# PortiloopV2Altium_Sch.net
KiCad netlist of a schematic drawn in Altium Designer
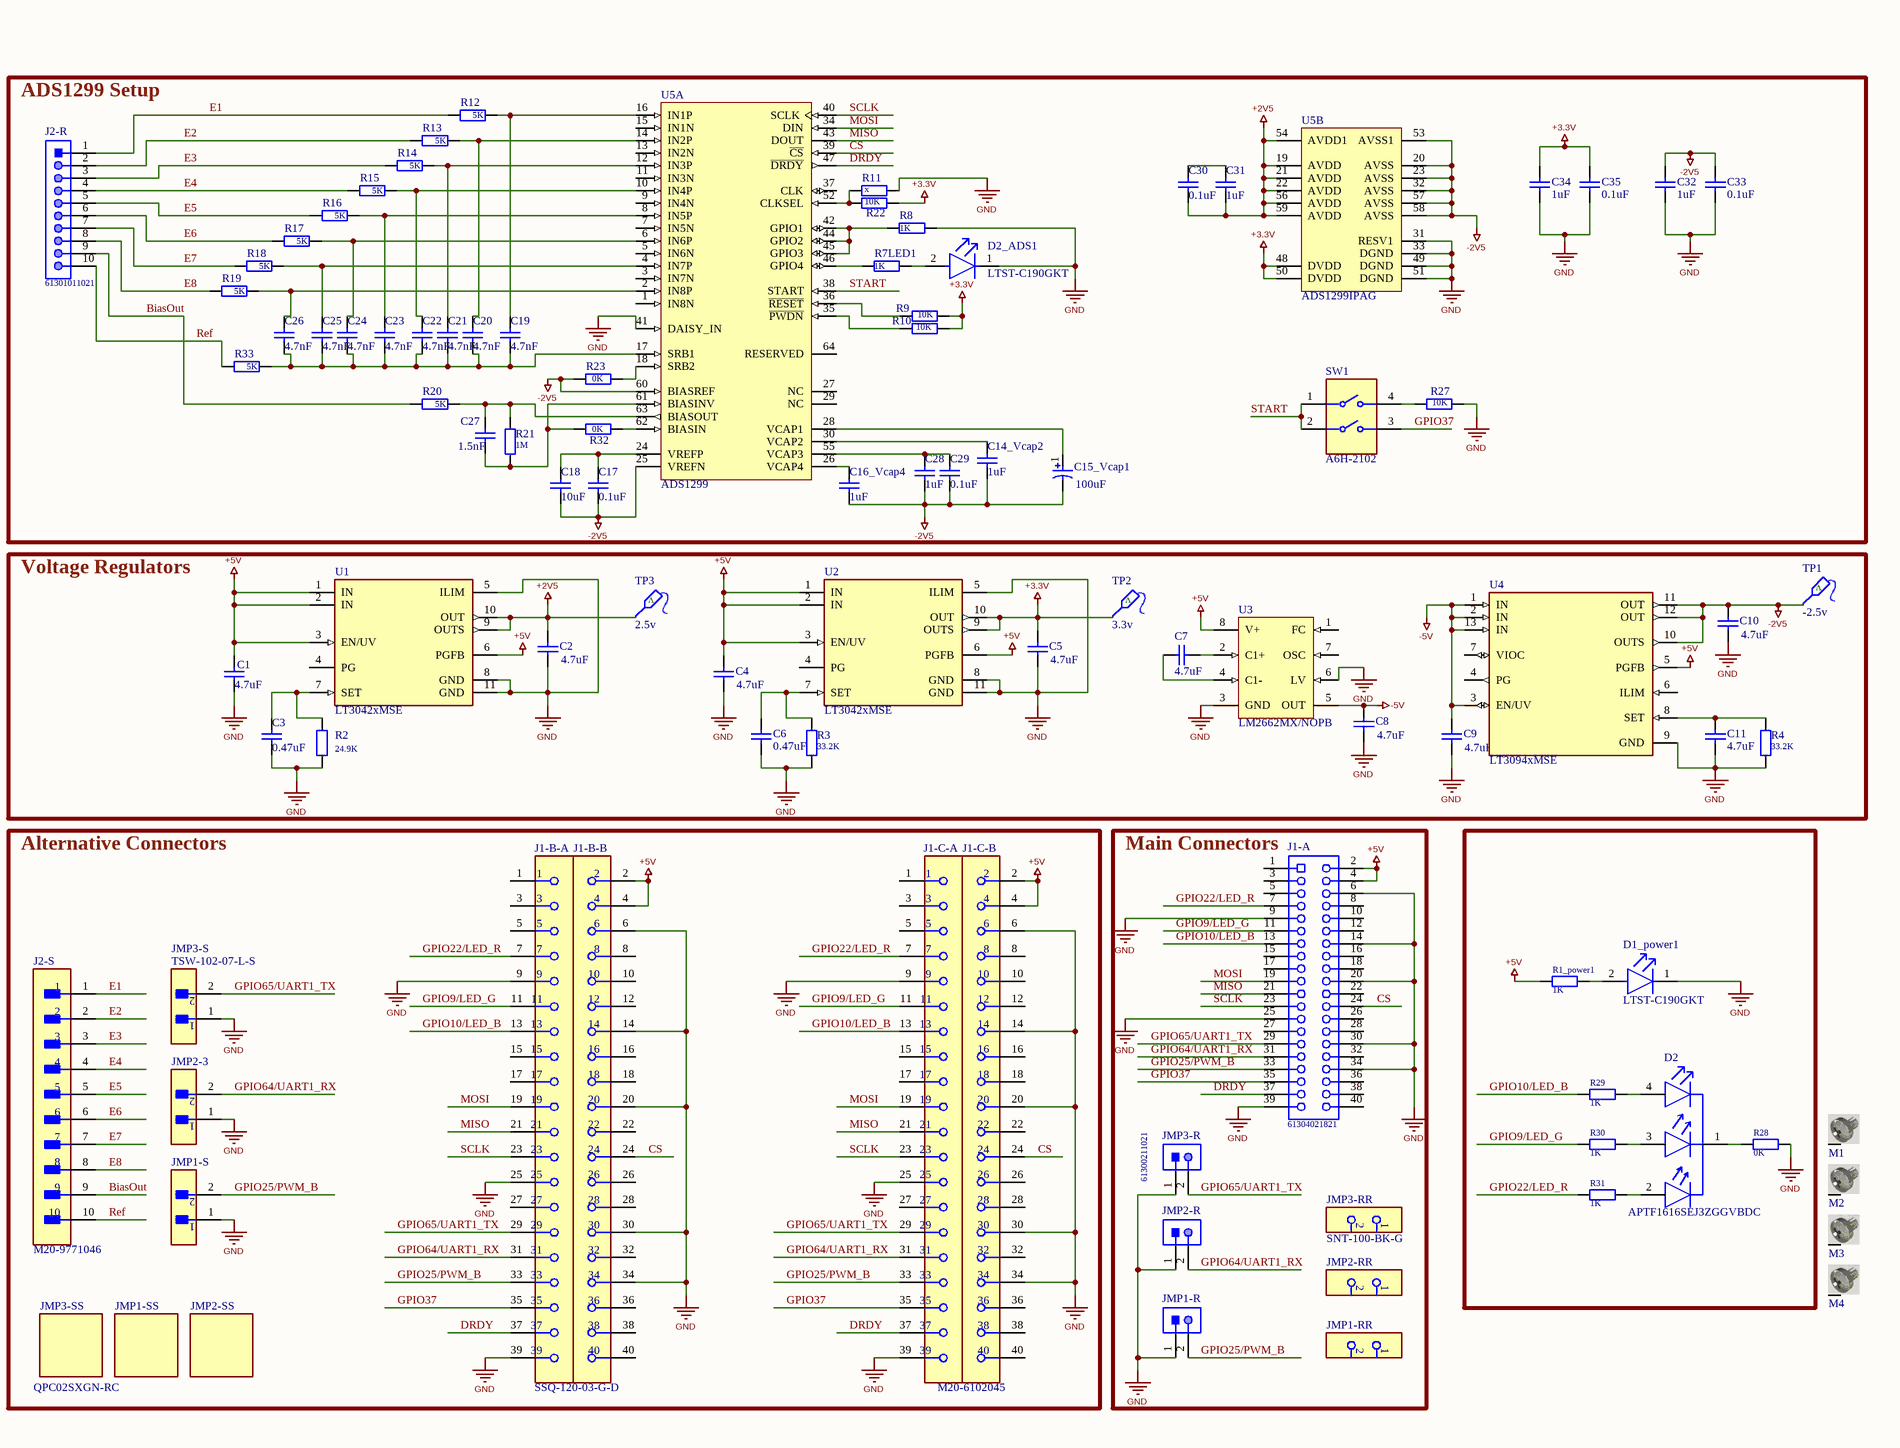
[diagram p0: PortiloopV2Altium_Sch.SchDoc, right]

(export (version "E")
  (design (tool "Eeschema 10.0.6"))
  (components
    (comp (ref "C1")
      (value "4.7uF")
      (footprint "C1206")
      (fields (field (name "Comment") "4.7mkf") (field (name "PUBLISHER") "Altium Limited"))
      (libsource (lib "Miscellaneous Devices") (part "Cap Semi"))
    )
    (comp (ref "C2")
      (value "4.7uF")
      (footprint "C1206")
      (fields (field (name "Comment") "4.7mkf") (field (name "PUBLISHER") "Altium Limited"))
      (libsource (lib "Miscellaneous Devices") (part "Cap Semi"))
    )
    (comp (ref "C3")
      (value "0.47uF")
      (footprint "1608[0603]")
      (fields (field (name "Comment") "0.47mkf") (field (name "PUBLISHER") "Altium Limited"))
      (libsource (lib "Miscellaneous Devices") (part "Cap Semi"))
    )
    (comp (ref "C4")
      (value "4.7uF")
      (footprint "C1206")
      (fields (field (name "Comment") "4.7mkf") (field (name "PUBLISHER") "Altium Limited"))
      (libsource (lib "Miscellaneous Devices") (part "Cap Semi"))
    )
    (comp (ref "C5")
      (value "4.7uF")
      (footprint "C1206")
      (fields (field (name "Comment") "4.7mkf") (field (name "PUBLISHER") "Altium Limited"))
      (libsource (lib "Miscellaneous Devices") (part "Cap Semi"))
    )
    (comp (ref "C6")
      (value "0.47uF")
      (footprint "1608[0603]")
      (fields (field (name "Comment") "0.47mkf") (field (name "PUBLISHER") "Altium Limited"))
      (libsource (lib "Miscellaneous Devices") (part "Cap Semi"))
    )
    (comp (ref "C7")
      (value "4.7uF")
      (footprint "C1206")
      (fields (field (name "Comment") "4.7mkf") (field (name "PUBLISHER") "Altium Limited"))
      (libsource (lib "Miscellaneous Devices") (part "Cap Semi"))
    )
    (comp (ref "C8")
      (value "4.7uF")
      (footprint "C1206")
      (fields (field (name "Comment") "4.7mkf") (field (name "PUBLISHER") "Altium Limited"))
      (libsource (lib "Miscellaneous Devices") (part "Cap Semi"))
    )
    (comp (ref "C9")
      (value "4.7uF")
      (footprint "C1206")
      (fields (field (name "Comment") "4.7mkf") (field (name "PUBLISHER") "Altium Limited"))
      (libsource (lib "Miscellaneous Devices") (part "Cap Semi"))
    )
    (comp (ref "C10")
      (value "4.7uF")
      (footprint "C1206")
      (fields (field (name "Comment") "4.7mkf") (field (name "PUBLISHER") "Altium Limited"))
      (libsource (lib "Miscellaneous Devices") (part "Cap Semi"))
    )
    (comp (ref "C11")
      (value "4.7uF")
      (footprint "C1206")
      (fields (field (name "Comment") "4.7mkf") (field (name "PUBLISHER") "Altium Limited"))
      (libsource (lib "Miscellaneous Devices") (part "Cap Semi"))
    )
    (comp (ref "C14_Vcap2")
      (value "1uF")
      (footprint "1608[0603]")
      (fields (field (name "Comment") "1mkf") (field (name "PUBLISHER") "Altium Limited"))
      (libsource (lib "Miscellaneous Devices") (part "Cap Semi"))
    )
    (comp (ref "C15_Vcap1")
      (value "100mkf")
      (footprint "KEMT-T491-D_M")
      (description "Capacitor, Tantalum, 100 uF, +/- 10%, -55 to 125 degC, 2-Pin SMD, RoHS, Tape and Reel")
      (fields (field (name "TOLERANCE") "20%") (field (name "CAPACITANCE") "100uF"))
      (libsource (lib "Altium Content Vault") (part "CAP-P-2"))
    )
    (comp (ref "C16_Vcap4")
      (value "1uF")
      (footprint "1608[0603]")
      (fields (field (name "Comment") "1mkf") (field (name "PUBLISHER") "Altium Limited"))
      (libsource (lib "Miscellaneous Devices") (part "Cap Semi"))
    )
    (comp (ref "C17")
      (value "0.1uF")
      (footprint "1608[0603]")
      (fields (field (name "Comment") "0.1mkf") (field (name "PUBLISHER") "Altium Limited"))
      (libsource (lib "Miscellaneous Devices") (part "Cap Semi"))
    )
    (comp (ref "C18")
      (value "10uF")
      (footprint "C1206")
      (fields (field (name "Comment") "10mkf") (field (name "PUBLISHER") "Altium Limited"))
      (libsource (lib "Miscellaneous Devices") (part "Cap Semi"))
    )
    (comp (ref "C19")
      (value "4.7nF")
      (footprint "1608[0603]")
      (fields (field (name "Comment") "4.7nf") (field (name "PUBLISHER") "Altium Limited"))
      (libsource (lib "Miscellaneous Devices") (part "Cap Semi"))
    )
    (comp (ref "C20")
      (value "4.7nF")
      (footprint "1608[0603]")
      (fields (field (name "Comment") "4.7nf") (field (name "PUBLISHER") "Altium Limited"))
      (libsource (lib "Miscellaneous Devices") (part "Cap Semi"))
    )
    (comp (ref "C21")
      (value "4.7nF")
      (footprint "1608[0603]")
      (fields (field (name "Comment") "4.7nf") (field (name "PUBLISHER") "Altium Limited"))
      (libsource (lib "Miscellaneous Devices") (part "Cap Semi"))
    )
    (comp (ref "C22")
      (value "4.7nF")
      (footprint "1608[0603]")
      (fields (field (name "Comment") "4.7nf") (field (name "PUBLISHER") "Altium Limited"))
      (libsource (lib "Miscellaneous Devices") (part "Cap Semi"))
    )
    (comp (ref "C23")
      (value "4.7nF")
      (footprint "1608[0603]")
      (fields (field (name "Comment") "4.7nf") (field (name "PUBLISHER") "Altium Limited"))
      (libsource (lib "Miscellaneous Devices") (part "Cap Semi"))
    )
    (comp (ref "C24")
      (value "4.7nF")
      (footprint "1608[0603]")
      (fields (field (name "Comment") "4.7nf") (field (name "PUBLISHER") "Altium Limited"))
      (libsource (lib "Miscellaneous Devices") (part "Cap Semi"))
    )
    (comp (ref "C25")
      (value "4.7nF")
      (footprint "1608[0603]")
      (fields (field (name "Comment") "4.7nf") (field (name "PUBLISHER") "Altium Limited"))
      (libsource (lib "Miscellaneous Devices") (part "Cap Semi"))
    )
    (comp (ref "C26")
      (value "4.7nF")
      (footprint "1608[0603]")
      (fields (field (name "Comment") "4.7nf") (field (name "PUBLISHER") "Altium Limited"))
      (libsource (lib "Miscellaneous Devices") (part "Cap Semi"))
    )
    (comp (ref "C27")
      (value "1.5nF")
      (footprint "1608[0603]")
      (fields (field (name "Comment") "1.5nf") (field (name "PUBLISHER") "Altium Limited"))
      (libsource (lib "Miscellaneous Devices") (part "Cap Semi"))
    )
    (comp (ref "C28")
      (value "1uF")
      (footprint "1608[0603]")
      (fields (field (name "Comment") "1mkf") (field (name "PUBLISHER") "Altium Limited"))
      (libsource (lib "Miscellaneous Devices") (part "Cap Semi"))
    )
    (comp (ref "C29")
      (value "0.1uF")
      (footprint "1608[0603]")
      (fields (field (name "Comment") "0.1mkf") (field (name "PUBLISHER") "Altium Limited"))
      (libsource (lib "Miscellaneous Devices") (part "Cap Semi"))
    )
    (comp (ref "C30")
      (value "0.1uF")
      (footprint "1608[0603]")
      (fields (field (name "Comment") "0.1mkf") (field (name "PUBLISHER") "Altium Limited"))
      (libsource (lib "Miscellaneous Devices") (part "Cap Semi"))
    )
    (comp (ref "C31")
      (value "1uF")
      (footprint "1608[0603]")
      (fields (field (name "Comment") "1mkf") (field (name "PUBLISHER") "Altium Limited"))
      (libsource (lib "Miscellaneous Devices") (part "Cap Semi"))
    )
    (comp (ref "C32")
      (value "1uF")
      (footprint "1608[0603]")
      (fields (field (name "Comment") "1mkf") (field (name "PUBLISHER") "Altium Limited"))
      (libsource (lib "Miscellaneous Devices") (part "Cap Semi"))
    )
    (comp (ref "C33")
      (value "0.1uF")
      (footprint "1608[0603]")
      (fields (field (name "Comment") "0.1mkf") (field (name "PUBLISHER") "Altium Limited"))
      (libsource (lib "Miscellaneous Devices") (part "Cap Semi"))
    )
    (comp (ref "C34")
      (value "1uF")
      (footprint "1608[0603]")
      (fields (field (name "Comment") "1mkf") (field (name "PUBLISHER") "Altium Limited"))
      (libsource (lib "Miscellaneous Devices") (part "Cap Semi"))
    )
    (comp (ref "C35")
      (value "0.1uF")
      (footprint "1608[0603]")
      (fields (field (name "Comment") "0.1mkf") (field (name "PUBLISHER") "Altium Limited"))
      (libsource (lib "Miscellaneous Devices") (part "Cap Semi"))
    )
    (comp (ref "D1_power1")
      (value "LTST-C190GKT")
      (footprint "FP-LTST-C190GKT-MFG")
      (description "LED GREEN CLEAR CHIP SMD")
      (fields (field (name "VOLTAGE") "2V"))
      (libsource (lib "Altium Content Vault") (part "8706943c75ba83719d021d2fdc84c58"))
    )
    (comp (ref "D2")
      (value "APTF1616SEJ3ZGGVBDC")
      (footprint "FP-APTF1616SEJ3ZGGVBDC-MFG")
      (description "LED RGB CLEAR 4SMD")
      (libsource (lib "Altium Content Vault") (part "09016a64638d3f35f69863a61e92420"))
    )
    (comp (ref "D2_ADS1")
      (value "LTST-C190GKT")
      (footprint "FP-LTST-C190GKT-MFG")
      (description "LED GREEN CLEAR CHIP SMD")
      (fields (field (name "VOLTAGE") "2V"))
      (libsource (lib "Altium Content Vault") (part "8706943c75ba83719d021d2fdc84c58"))
    )
    (comp (ref "J1-A")
      (value "61304021821")
      (footprint "61304021821")
      (description "THT Vertical Socket Header WR-PHD, Pitch 2.54 mm, Dual Row, 40 pins")
      (fields (field (name "MANUFACTURER") "Wurth Elektronik") (field (name "PUBLISHER") "WurthElektronik"))
      (libsource (lib "Altium Content Vault") (part "WE-CN-2P-F-R40"))
    )
    (comp (ref "J1-B-")
      (value "SSQ-120-03-G-D")
      (footprint "FP-SSQ-120-03-G-D-MFG")
      (description "CONN RCPT 40POS 0.1 GOLD PCB")
      (libsource (lib "Altium Content Vault") (part "7acf1c4a8db21028d11741a46a6ec78"))
    )
    (comp (ref "J1-C-")
      (value "M20-6102045")
      (footprint "FP-M20-6102045-MFG")
      (description "CONN STKTHRU PC/104 40POS PCB")
      (libsource (lib "Altium Content Vault") (part "7acf1c4a8db21028d11741a46a6ec78"))
    )
    (comp (ref "J2-R")
      (value "61301011021")
      (footprint "61301011021")
      (description "THT Angled Pin Header WR-PHD, Pitch 2.54 mm, Single Row, 10 pins")
      (fields (field (name "MANUFACTURER") "Wurth Elektronik") (field (name "PUBLISHER") "WurthElektronik"))
      (libsource (lib "Altium Content Vault") (part "WE-CN-1P-M-R10"))
    )
    (comp (ref "J2-S")
      (value "M20-9771046")
      (footprint "FP-M20-9771046-MFG")
      (description "CONN HEADER VERT 10POS 2.54MM")
      (libsource (lib "Altium Content Vault") (part "aee40dc8b284c03a16094555aa210be"))
    )
    (comp (ref "JMP1-R")
      (value "61300211021")
      (footprint "61300211021")
      (description "THT Angled Pin Header WR-PHD, Pitch 2.54 mm, Single Row, 2 pins")
      (fields (field (name "MANUFACTURER") "Wurth Elektronik") (field (name "PUBLISHER") "WurthElektronik"))
      (libsource (lib "Altium Content Vault") (part "WE-CN-1P-M-R2"))
    )
    (comp (ref "JMP1-RR")
      (value "SNT-100-BK-G")
      (footprint "FP-SNT-100-BK-G-MFG")
      (description "CONN SHUNT 2POS")
      (libsource (lib "Altium Content Vault") (part "245d4dded57b275ea2dfe9722bb6e84"))
    )
    (comp (ref "JMP1-S")
      (value "TSW-102-07-L-S")
      (footprint "FP-TSW-102-07-L-S-MFG")
      (description "CONN HEADER VERT 2POS 2.54MM")
      (libsource (lib "Altium Content Vault") (part "3bc925449376181038e59eaffc5286c"))
    )
    (comp (ref "JMP1-SS")
      (value "QPC02SXGN-RC")
      (footprint "FP-QPC02SXGN-RC-MFG")
      (description "CONN JUMPER SHORTING .100\" GOLD")
      (fields
        (field (name "MANUFACTURER") "Sullins")
        (field (name "OCTOPART") "https://octopart.com/qpc02sxgn-rc-sullins-19878795")
      )
      (libsource (lib "Altium Content Vault") (part "87292ac8601c6cf2061292f5bede09e"))
    )
    (comp (ref "JMP2-3")
      (value "TSW-102-07-L-S")
      (footprint "FP-TSW-102-07-L-S-MFG")
      (description "CONN HEADER VERT 2POS 2.54MM")
      (libsource (lib "Altium Content Vault") (part "3bc925449376181038e59eaffc5286c"))
    )
    (comp (ref "JMP2-R")
      (value "61300211021")
      (footprint "61300211021")
      (description "THT Angled Pin Header WR-PHD, Pitch 2.54 mm, Single Row, 2 pins")
      (fields (field (name "MANUFACTURER") "Wurth Elektronik") (field (name "PUBLISHER") "WurthElektronik"))
      (libsource (lib "Altium Content Vault") (part "WE-CN-1P-M-R2"))
    )
    (comp (ref "JMP2-RR")
      (value "SNT-100-BK-G")
      (footprint "FP-SNT-100-BK-G-MFG")
      (description "CONN SHUNT 2POS")
      (libsource (lib "Altium Content Vault") (part "245d4dded57b275ea2dfe9722bb6e84"))
    )
    (comp (ref "JMP2-SS")
      (value "QPC02SXGN-RC")
      (footprint "FP-QPC02SXGN-RC-MFG")
      (description "CONN JUMPER SHORTING .100\" GOLD")
      (fields
        (field (name "MANUFACTURER") "Sullins")
        (field (name "OCTOPART") "https://octopart.com/qpc02sxgn-rc-sullins-19878795")
      )
      (libsource (lib "Altium Content Vault") (part "87292ac8601c6cf2061292f5bede09e"))
    )
    (comp (ref "JMP3-R")
      (value "61300211021")
      (footprint "61300211021")
      (description "THT Angled Pin Header WR-PHD, Pitch 2.54 mm, Single Row, 2 pins")
      (fields (field (name "MANUFACTURER") "Wurth Elektronik") (field (name "PUBLISHER") "WurthElektronik"))
      (libsource (lib "Altium Content Vault") (part "WE-CN-1P-M-R2"))
    )
    (comp (ref "JMP3-RR")
      (value "SNT-100-BK-G")
      (footprint "FP-SNT-100-BK-G-MFG")
      (description "CONN SHUNT 2POS")
      (libsource (lib "Altium Content Vault") (part "245d4dded57b275ea2dfe9722bb6e84"))
    )
    (comp (ref "JMP3-S")
      (value "TSW-102-07-L-S")
      (footprint "FP-TSW-102-07-L-S-MFG")
      (description "CONN HEADER VERT 2POS 2.54MM")
      (libsource (lib "Altium Content Vault") (part "3bc925449376181038e59eaffc5286c"))
    )
    (comp (ref "JMP3-SS")
      (value "QPC02SXGN-RC")
      (footprint "FP-QPC02SXGN-RC-MFG")
      (description "CONN JUMPER SHORTING .100\" GOLD")
      (fields
        (field (name "MANUFACTURER") "Sullins")
        (field (name "OCTOPART") "https://octopart.com/qpc02sxgn-rc-sullins-19878795")
      )
      (libsource (lib "Altium Content Vault") (part "87292ac8601c6cf2061292f5bede09e"))
    )
    (comp (ref "M1")
      (value "Screw")
      (footprint "Board Screw_No Silk")
      (description "Board Screw With Spacer")
      (libsource (lib "Lib_marjani") (part "Board Screw"))
    )
    (comp (ref "M2")
      (value "Screw")
      (footprint "Board Screw_No Silk")
      (description "Board Screw With Spacer")
      (libsource (lib "Lib_marjani") (part "Board Screw"))
    )
    (comp (ref "M3")
      (value "Screw")
      (footprint "Board Screw_No Silk")
      (description "Board Screw With Spacer")
      (libsource (lib "Lib_marjani") (part "Board Screw"))
    )
    (comp (ref "M4")
      (value "Screw")
      (footprint "Board Screw_No Silk")
      (description "Board Screw With Spacer")
      (libsource (lib "Lib_marjani") (part "Board Screw"))
    )
    (comp (ref "R1_power1")
      (value "1K")
      (footprint "1608[0603]")
      (description "Resistor")
      (fields (field (name "PUBLISHER") "Altium Limited"))
      (libsource (lib "") (part "Res2_2"))
    )
    (comp (ref "R2")
      (value "24.9K")
      (footprint "1608[0603]")
      (description "Resistor")
      (fields (field (name "PUBLISHER") "Altium Limited"))
      (libsource (lib "Miscellaneous Devices") (part "Res2"))
    )
    (comp (ref "R3")
      (value "33.2K")
      (footprint "1608[0603]")
      (description "Resistor")
      (fields (field (name "PUBLISHER") "Altium Limited"))
      (libsource (lib "Miscellaneous Devices") (part "Res2"))
    )
    (comp (ref "R4")
      (value "33.2K")
      (footprint "1608[0603]")
      (description "Resistor")
      (fields (field (name "PUBLISHER") "Altium Limited"))
      (libsource (lib "Miscellaneous Devices") (part "Res2"))
    )
    (comp (ref "R7LED1")
      (value "1K")
      (footprint "1608[0603]")
      (description "Resistor")
      (fields (field (name "PUBLISHER") "Altium Limited"))
      (libsource (lib "") (part "Res2_1"))
    )
    (comp (ref "R8")
      (value "1K")
      (footprint "1608[0603]")
      (description "Resistor")
      (fields (field (name "PUBLISHER") "Altium Limited"))
      (libsource (lib "") (part "Res2_1"))
    )
    (comp (ref "R9")
      (value "10K")
      (footprint "1608[0603]")
      (description "Resistor")
      (fields (field (name "PUBLISHER") "Altium Limited"))
      (libsource (lib "") (part "Res2_2"))
    )
    (comp (ref "R10")
      (value "10K")
      (footprint "1608[0603]")
      (description "Resistor")
      (fields (field (name "PUBLISHER") "Altium Limited"))
      (libsource (lib "") (part "Res2_2"))
    )
    (comp (ref "R11")
      (value "x")
      (footprint "1608[0603]")
      (description "Not Connected")
      (fields (field (name "PUBLISHER") "Altium Limited"))
      (libsource (lib "") (part "Res2_2"))
    )
    (comp (ref "R12")
      (value "5K")
      (footprint "1608[0603]")
      (description "Resistor")
      (fields (field (name "PUBLISHER") "Altium Limited"))
      (libsource (lib "") (part "Res2_1"))
    )
    (comp (ref "R13")
      (value "5K")
      (footprint "1608[0603]")
      (description "Resistor")
      (fields (field (name "PUBLISHER") "Altium Limited"))
      (libsource (lib "") (part "Res2_1"))
    )
    (comp (ref "R14")
      (value "5K")
      (footprint "1608[0603]")
      (description "Resistor")
      (fields (field (name "PUBLISHER") "Altium Limited"))
      (libsource (lib "") (part "Res2_1"))
    )
    (comp (ref "R15")
      (value "5K")
      (footprint "1608[0603]")
      (description "Resistor")
      (fields (field (name "PUBLISHER") "Altium Limited"))
      (libsource (lib "") (part "Res2_1"))
    )
    (comp (ref "R16")
      (value "5K")
      (footprint "1608[0603]")
      (description "Resistor")
      (fields (field (name "PUBLISHER") "Altium Limited"))
      (libsource (lib "") (part "Res2_1"))
    )
    (comp (ref "R17")
      (value "5K")
      (footprint "1608[0603]")
      (description "Resistor")
      (fields (field (name "PUBLISHER") "Altium Limited"))
      (libsource (lib "") (part "Res2_1"))
    )
    (comp (ref "R18")
      (value "5K")
      (footprint "1608[0603]")
      (description "Resistor")
      (fields (field (name "PUBLISHER") "Altium Limited"))
      (libsource (lib "") (part "Res2_1"))
    )
    (comp (ref "R19")
      (value "5K")
      (footprint "1608[0603]")
      (description "Resistor")
      (fields (field (name "PUBLISHER") "Altium Limited"))
      (libsource (lib "") (part "Res2_1"))
    )
    (comp (ref "R20")
      (value "5K")
      (footprint "1608[0603]")
      (description "Resistor")
      (fields (field (name "PUBLISHER") "Altium Limited"))
      (libsource (lib "") (part "Res2_1"))
    )
    (comp (ref "R21")
      (value "1M")
      (footprint "1608[0603]")
      (description "Resistor")
      (fields (field (name "PUBLISHER") "Altium Limited"))
      (libsource (lib "Miscellaneous Devices") (part "Res2"))
    )
    (comp (ref "R22")
      (value "10K")
      (footprint "1608[0603]")
      (description "Resistor")
      (fields (field (name "PUBLISHER") "Altium Limited"))
      (libsource (lib "") (part "Res2_2"))
    )
    (comp (ref "R23")
      (value "0K")
      (footprint "1608[0603]")
      (description "Resistor")
      (fields (field (name "PUBLISHER") "Altium Limited"))
      (libsource (lib "") (part "Res2_2"))
    )
    (comp (ref "R27")
      (value "10K")
      (footprint "1608[0603]")
      (description "Resistor")
      (fields (field (name "PUBLISHER") "Altium Limited"))
      (libsource (lib "") (part "Res2_2"))
    )
    (comp (ref "R28")
      (value "0K")
      (footprint "1608[0603]")
      (description "Resistor")
      (fields (field (name "PUBLISHER") "Altium Limited"))
      (libsource (lib "") (part "Res2_2"))
    )
    (comp (ref "R29")
      (value "1K")
      (footprint "1608[0603]")
      (description "Resistor")
      (fields (field (name "PUBLISHER") "Altium Limited"))
      (libsource (lib "") (part "Res2_2"))
    )
    (comp (ref "R30")
      (value "1K")
      (footprint "1608[0603]")
      (description "Resistor")
      (fields (field (name "PUBLISHER") "Altium Limited"))
      (libsource (lib "") (part "Res2_2"))
    )
    (comp (ref "R31")
      (value "1K")
      (footprint "1608[0603]")
      (description "Resistor")
      (fields (field (name "PUBLISHER") "Altium Limited"))
      (libsource (lib "") (part "Res2_2"))
    )
    (comp (ref "R32")
      (value "0K")
      (footprint "1608[0603]")
      (description "Resistor")
      (fields (field (name "PUBLISHER") "Altium Limited"))
      (libsource (lib "") (part "Res2_2"))
    )
    (comp (ref "R33")
      (value "5K")
      (footprint "1608[0603]")
      (description "Resistor")
      (fields (field (name "PUBLISHER") "Altium Limited"))
      (libsource (lib "") (part "Res2_1"))
    )
    (comp (ref "SW1")
      (value "A6H-2102")
      (footprint "FP-A6H-2102-MFG")
      (description "SWITCH SLIDE DIP SPST 25MA 24V")
      (libsource (lib "Altium Content Vault") (part "070a973bb9dfaf4112c7cb8da95b8f6"))
    )
    (comp (ref "TP1")
      (value "-2.5v")
      (footprint "TESTPOINT1")
      (description "Test Point")
      (libsource (lib "My Library") (part "Test Point"))
    )
    (comp (ref "TP2")
      (value "3.3v")
      (footprint "TESTPOINT1")
      (description "Test Point")
      (libsource (lib "My Library") (part "Test Point"))
    )
    (comp (ref "TP3")
      (value "2.5v")
      (footprint "TESTPOINT1")
      (description "Test Point")
      (libsource (lib "My Library") (part "Test Point"))
    )
    (comp (ref "U1")
      (value "LT3042xMSE")
      (footprint "FP-MSE-10-05-08-1664-IPC_C")
      (description "IC REG LIN POS ADJ 200MA 10MSOP")
      (libsource (lib "Altium Content Vault") (part "617b45537435f4b0c995ef5898f6a34"))
    )
    (comp (ref "U2")
      (value "LT3042xMSE")
      (footprint "FP-MSE-10-05-08-1664-IPC_C")
      (description "IC REG LIN POS ADJ 200MA 10MSOP")
      (libsource (lib "Altium Content Vault") (part "617b45537435f4b0c995ef5898f6a34"))
    )
    (comp (ref "U3")
      (value "LM2662MX/NOPB")
      (footprint "D0008A_M")
      (description "Switched Capacitor Voltage Converter, 8-pin Narrow SOIC, Pb-Free")
      (fields (field (name "MANUFACTURER") "Texas Instruments"))
      (libsource (lib "Altium Content Vault") (part "PM-CHP-LM2660M-8"))
    )
    (comp (ref "U4")
      (value "LT3094xMSE")
      (footprint "FP-MSE-12-05-08-1666-IPC_A")
      (description "IC REG LIN NEG ADJ 500MA 12MSOP")
      (libsource (lib "Altium Content Vault") (part "4f09b0e52ede19156f7e08ace673db3"))
    )
    (comp (ref "U5")
      (value "ADS1299")
      (footprint "PAG0064A_M")
      (fields (field (name "MANUFACTURER") "Texas Instruments") (field (name "PARTNUMBER") "ADS1299IPAG"))
      (libsource (lib "") (part "TI-ADS1299-PAG-64_1"))
    )
  )
  (nets
    (net (code "1") (name "+2V5") (class "Default")
      (node (ref "C2") (pin "2") (pinfunction "2_2") (pintype "passive"))
      (node (ref "C30") (pin "2") (pinfunction "2_2") (pintype "passive"))
      (node (ref "C31") (pin "2") (pinfunction "2_2") (pintype "passive"))
      (node (ref "TP3") (pin "1") (pinfunction "T_1") (pintype "passive"))
      (node (ref "U1") (pin "10") (pinfunction "OUT_10") (pintype "output"))
      (node (ref "U1") (pin "9") (pinfunction "OUTS_9") (pintype "output"))
      (node (ref "U5") (pin "19") (pinfunction "AVDD_19") (pintype "power_in"))
      (node (ref "U5") (pin "21") (pinfunction "AVDD_21") (pintype "power_in"))
      (node (ref "U5") (pin "22") (pinfunction "AVDD_22") (pintype "power_in"))
      (node (ref "U5") (pin "54") (pinfunction "AVDD1_54") (pintype "power_in"))
      (node (ref "U5") (pin "56") (pinfunction "AVDD_56") (pintype "power_in"))
      (node (ref "U5") (pin "59") (pinfunction "AVDD_59") (pintype "power_in"))
    )
    (net (code "2") (name "+3.3V") (class "Default")
      (node (ref "C34") (pin "2") (pinfunction "2_2") (pintype "passive"))
      (node (ref "C35") (pin "2") (pinfunction "2_2") (pintype "passive"))
      (node (ref "C5") (pin "2") (pinfunction "2_2") (pintype "passive"))
      (node (ref "R10") (pin "1") (pinfunction "1_1") (pintype "passive"))
      (node (ref "R22") (pin "1") (pinfunction "1_1") (pintype "passive"))
      (node (ref "R9") (pin "1") (pinfunction "1_1") (pintype "passive"))
      (node (ref "TP2") (pin "1") (pinfunction "T_1") (pintype "passive"))
      (node (ref "U2") (pin "10") (pinfunction "OUT_10") (pintype "output"))
      (node (ref "U2") (pin "9") (pinfunction "OUTS_9") (pintype "output"))
      (node (ref "U5") (pin "48") (pinfunction "DVDD_48") (pintype "power_in"))
      (node (ref "U5") (pin "50") (pinfunction "DVDD_50") (pintype "power_in"))
    )
    (net (code "3") (name "+5V") (class "Default")
      (node (ref "C1") (pin "2") (pinfunction "2_2") (pintype "passive"))
      (node (ref "C4") (pin "2") (pinfunction "2_2") (pintype "passive"))
      (node (ref "J1-A") (pin "2") (pinfunction "2_2") (pintype "passive"))
      (node (ref "J1-A") (pin "4") (pinfunction "4_4") (pintype "passive"))
      (node (ref "J1-B-") (pin "2") (pinfunction "2_2") (pintype "passive"))
      (node (ref "J1-B-") (pin "4") (pinfunction "4_4") (pintype "passive"))
      (node (ref "J1-C-") (pin "2") (pinfunction "2_2") (pintype "passive"))
      (node (ref "J1-C-") (pin "4") (pinfunction "4_4") (pintype "passive"))
      (node (ref "R1_power1") (pin "2") (pinfunction "2_2") (pintype "passive"))
      (node (ref "U1") (pin "1") (pinfunction "IN_1") (pintype "power_in"))
      (node (ref "U1") (pin "2") (pinfunction "IN_2") (pintype "power_in"))
      (node (ref "U1") (pin "3") (pinfunction "EN/UV_3") (pintype "input"))
      (node (ref "U1") (pin "6") (pinfunction "PGFB_6") (pintype "passive"))
      (node (ref "U2") (pin "1") (pinfunction "IN_1") (pintype "power_in"))
      (node (ref "U2") (pin "2") (pinfunction "IN_2") (pintype "power_in"))
      (node (ref "U2") (pin "3") (pinfunction "EN/UV_3") (pintype "input"))
      (node (ref "U2") (pin "6") (pinfunction "PGFB_6") (pintype "passive"))
      (node (ref "U3") (pin "8") (pinfunction "V+_8") (pintype "power_in"))
      (node (ref "U4") (pin "5") (pinfunction "PGFB_5") (pintype "output"))
    )
    (net (code "4") (name "-2V5") (class "Default")
      (node (ref "C10") (pin "2") (pinfunction "2_2") (pintype "passive"))
      (node (ref "C14_Vcap2") (pin "1") (pinfunction "1_1") (pintype "passive"))
      (node (ref "C15_Vcap1") (pin "2") (pinfunction "2_2") (pintype "passive"))
      (node (ref "C16_Vcap4") (pin "1") (pinfunction "1_1") (pintype "passive"))
      (node (ref "C17") (pin "2") (pinfunction "2_2") (pintype "passive"))
      (node (ref "C18") (pin "1") (pinfunction "1_1") (pintype "passive"))
      (node (ref "C28") (pin "1") (pinfunction "1_1") (pintype "passive"))
      (node (ref "C29") (pin "1") (pinfunction "1_1") (pintype "passive"))
      (node (ref "C32") (pin "2") (pinfunction "2_2") (pintype "passive"))
      (node (ref "C33") (pin "2") (pinfunction "2_2") (pintype "passive"))
      (node (ref "R23") (pin "2") (pinfunction "2_2") (pintype "passive"))
      (node (ref "TP1") (pin "1") (pinfunction "T_1") (pintype "passive"))
      (node (ref "U4") (pin "10") (pinfunction "OUTS_10") (pintype "output"))
      (node (ref "U4") (pin "11") (pinfunction "OUT_11") (pintype "output"))
      (node (ref "U4") (pin "12") (pinfunction "OUT_12") (pintype "output"))
      (node (ref "U5") (pin "20") (pinfunction "AVSS_20") (pintype "power_in"))
      (node (ref "U5") (pin "23") (pinfunction "AVSS_23") (pintype "power_in"))
      (node (ref "U5") (pin "25") (pinfunction "VREFN_25") (pintype "passive"))
      (node (ref "U5") (pin "32") (pinfunction "AVSS_32") (pintype "power_in"))
      (node (ref "U5") (pin "53") (pinfunction "AVSS1_53") (pintype "power_in"))
      (node (ref "U5") (pin "57") (pinfunction "AVSS_57") (pintype "power_in"))
      (node (ref "U5") (pin "58") (pinfunction "AVSS_58") (pintype "power_in"))
      (node (ref "U5") (pin "60") (pinfunction "BIASREF_60") (pintype "input"))
    )
    (net (code "5") (name "-5V") (class "Default")
      (node (ref "C8") (pin "2") (pinfunction "2_2") (pintype "passive"))
      (node (ref "C9") (pin "2") (pinfunction "2_2") (pintype "passive"))
      (node (ref "U3") (pin "5") (pinfunction "OUT_5") (pintype "power_in"))
      (node (ref "U4") (pin "1") (pinfunction "IN_1") (pintype "input"))
      (node (ref "U4") (pin "13") (pinfunction "IN_13") (pintype "input"))
      (node (ref "U4") (pin "2") (pinfunction "IN_2") (pintype "input"))
      (node (ref "U4") (pin "3") (pinfunction "EN/UV_3") (pintype "bidirectional"))
    )
    (net (code "6") (name "/BiasOut") (class "Default")
      (node (ref "J2-R") (pin "9") (pinfunction "9_9") (pintype "passive"))
      (node (ref "J2-S") (pin "9") (pinfunction "9_9") (pintype "passive"))
      (node (ref "R20") (pin "1") (pinfunction "1_1") (pintype "passive"))
    )
    (net (code "7") (name "/CS") (class "Default")
      (node (ref "J1-A") (pin "24") (pinfunction "24_24") (pintype "passive"))
      (node (ref "J1-B-") (pin "24") (pinfunction "24_24") (pintype "passive"))
      (node (ref "J1-C-") (pin "24") (pinfunction "24_24") (pintype "passive"))
      (node (ref "U5") (pin "39") (pinfunction "~{CS}_39") (pintype "input"))
    )
    (net (code "8") (name "/DRDY") (class "Default")
      (node (ref "J1-A") (pin "37") (pinfunction "37_37") (pintype "passive"))
      (node (ref "J1-B-") (pin "37") (pinfunction "37_37") (pintype "passive"))
      (node (ref "J1-C-") (pin "37") (pinfunction "37_37") (pintype "passive"))
      (node (ref "U5") (pin "47") (pinfunction "~{DRDY}_47") (pintype "output"))
    )
    (net (code "9") (name "/E1") (class "Default")
      (node (ref "J2-R") (pin "1") (pinfunction "1_1") (pintype "passive"))
      (node (ref "J2-S") (pin "1") (pinfunction "1_1") (pintype "passive"))
      (node (ref "R12") (pin "1") (pinfunction "1_1") (pintype "passive"))
    )
    (net (code "10") (name "/E2") (class "Default")
      (node (ref "J2-R") (pin "2") (pinfunction "2_2") (pintype "passive"))
      (node (ref "J2-S") (pin "2") (pinfunction "2_2") (pintype "passive"))
      (node (ref "R13") (pin "1") (pinfunction "1_1") (pintype "passive"))
    )
    (net (code "11") (name "/E3") (class "Default")
      (node (ref "J2-R") (pin "3") (pinfunction "3_3") (pintype "passive"))
      (node (ref "J2-S") (pin "3") (pinfunction "3_3") (pintype "passive"))
      (node (ref "R14") (pin "1") (pinfunction "1_1") (pintype "passive"))
    )
    (net (code "12") (name "/E4") (class "Default")
      (node (ref "J2-R") (pin "4") (pinfunction "4_4") (pintype "passive"))
      (node (ref "J2-S") (pin "4") (pinfunction "4_4") (pintype "passive"))
      (node (ref "R15") (pin "1") (pinfunction "1_1") (pintype "passive"))
    )
    (net (code "13") (name "/E5") (class "Default")
      (node (ref "J2-R") (pin "5") (pinfunction "5_5") (pintype "passive"))
      (node (ref "J2-S") (pin "5") (pinfunction "5_5") (pintype "passive"))
      (node (ref "R16") (pin "1") (pinfunction "1_1") (pintype "passive"))
    )
    (net (code "14") (name "/E6") (class "Default")
      (node (ref "J2-R") (pin "6") (pinfunction "6_6") (pintype "passive"))
      (node (ref "J2-S") (pin "6") (pinfunction "6_6") (pintype "passive"))
      (node (ref "R17") (pin "1") (pinfunction "1_1") (pintype "passive"))
    )
    (net (code "15") (name "/E7") (class "Default")
      (node (ref "J2-R") (pin "7") (pinfunction "7_7") (pintype "passive"))
      (node (ref "J2-S") (pin "7") (pinfunction "7_7") (pintype "passive"))
      (node (ref "R18") (pin "1") (pinfunction "1_1") (pintype "passive"))
    )
    (net (code "16") (name "/E8") (class "Default")
      (node (ref "J2-R") (pin "8") (pinfunction "8_8") (pintype "passive"))
      (node (ref "J2-S") (pin "8") (pinfunction "8_8") (pintype "passive"))
      (node (ref "R19") (pin "1") (pinfunction "1_1") (pintype "passive"))
    )
    (net (code "17") (name "/GPIO9{slash}LED_G") (class "Default")
      (node (ref "J1-A") (pin "11") (pinfunction "11_11") (pintype "passive"))
      (node (ref "J1-B-") (pin "11") (pinfunction "11_11") (pintype "passive"))
      (node (ref "J1-C-") (pin "11") (pinfunction "11_11") (pintype "passive"))
      (node (ref "R30") (pin "2") (pinfunction "2_2") (pintype "passive"))
    )
    (net (code "18") (name "/GPIO10{slash}LED_B") (class "Default")
      (node (ref "J1-A") (pin "13") (pinfunction "13_13") (pintype "passive"))
      (node (ref "J1-B-") (pin "13") (pinfunction "13_13") (pintype "passive"))
      (node (ref "J1-C-") (pin "13") (pinfunction "13_13") (pintype "passive"))
      (node (ref "R29") (pin "2") (pinfunction "2_2") (pintype "passive"))
    )
    (net (code "19") (name "/GPIO22{slash}LED_R") (class "Default")
      (node (ref "J1-A") (pin "7") (pinfunction "7_7") (pintype "passive"))
      (node (ref "J1-B-") (pin "7") (pinfunction "7_7") (pintype "passive"))
      (node (ref "J1-C-") (pin "7") (pinfunction "7_7") (pintype "passive"))
      (node (ref "R31") (pin "2") (pinfunction "2_2") (pintype "passive"))
    )
    (net (code "20") (name "/GPIO25{slash}PWM_B") (class "Default")
      (node (ref "J1-A") (pin "33") (pinfunction "33_33") (pintype "passive"))
      (node (ref "J1-B-") (pin "33") (pinfunction "33_33") (pintype "passive"))
      (node (ref "J1-C-") (pin "33") (pinfunction "33_33") (pintype "passive"))
      (node (ref "JMP1-R") (pin "2") (pinfunction "2_2") (pintype "passive"))
      (node (ref "JMP1-S") (pin "2") (pinfunction "2_2") (pintype "passive"))
    )
    (net (code "21") (name "/GPIO37") (class "Default")
      (node (ref "J1-A") (pin "35") (pinfunction "35_35") (pintype "passive"))
      (node (ref "J1-B-") (pin "35") (pinfunction "35_35") (pintype "passive"))
      (node (ref "J1-C-") (pin "35") (pinfunction "35_35") (pintype "passive"))
      (node (ref "SW1") (pin "3") (pinfunction "3_3") (pintype "passive"))
    )
    (net (code "22") (name "/GPIO64{slash}UART1_RX") (class "Default")
      (node (ref "J1-A") (pin "31") (pinfunction "31_31") (pintype "passive"))
      (node (ref "J1-B-") (pin "31") (pinfunction "31_31") (pintype "passive"))
      (node (ref "J1-C-") (pin "31") (pinfunction "31_31") (pintype "passive"))
      (node (ref "JMP2-3") (pin "2") (pinfunction "2_2") (pintype "passive"))
      (node (ref "JMP2-R") (pin "2") (pinfunction "2_2") (pintype "passive"))
    )
    (net (code "23") (name "/GPIO65{slash}UART1_TX") (class "Default")
      (node (ref "J1-A") (pin "29") (pinfunction "29_29") (pintype "passive"))
      (node (ref "J1-B-") (pin "29") (pinfunction "29_29") (pintype "passive"))
      (node (ref "J1-C-") (pin "29") (pinfunction "29_29") (pintype "passive"))
      (node (ref "JMP3-R") (pin "2") (pinfunction "2_2") (pintype "passive"))
      (node (ref "JMP3-S") (pin "2") (pinfunction "2_2") (pintype "passive"))
    )
    (net (code "24") (name "/MISO") (class "Default")
      (node (ref "J1-A") (pin "21") (pinfunction "21_21") (pintype "passive"))
      (node (ref "J1-B-") (pin "21") (pinfunction "21_21") (pintype "passive"))
      (node (ref "J1-C-") (pin "21") (pinfunction "21_21") (pintype "passive"))
      (node (ref "U5") (pin "43") (pinfunction "DOUT_43") (pintype "tri_state"))
    )
    (net (code "25") (name "/MOSI") (class "Default")
      (node (ref "J1-A") (pin "19") (pinfunction "19_19") (pintype "passive"))
      (node (ref "J1-B-") (pin "19") (pinfunction "19_19") (pintype "passive"))
      (node (ref "J1-C-") (pin "19") (pinfunction "19_19") (pintype "passive"))
      (node (ref "U5") (pin "34") (pinfunction "DIN_34") (pintype "input"))
    )
    (net (code "26") (name "/Ref") (class "Default")
      (node (ref "J2-R") (pin "10") (pinfunction "10_10") (pintype "passive"))
      (node (ref "J2-S") (pin "10") (pinfunction "10_10") (pintype "passive"))
      (node (ref "R33") (pin "1") (pinfunction "1_1") (pintype "passive"))
    )
    (net (code "27") (name "/SCLK") (class "Default")
      (node (ref "J1-A") (pin "23") (pinfunction "23_23") (pintype "passive"))
      (node (ref "J1-B-") (pin "23") (pinfunction "23_23") (pintype "passive"))
      (node (ref "J1-C-") (pin "23") (pinfunction "23_23") (pintype "passive"))
      (node (ref "U5") (pin "40") (pinfunction "SCLK_40") (pintype "input"))
    )
    (net (code "28") (name "/START") (class "Default")
      (node (ref "SW1") (pin "1") (pinfunction "1_1") (pintype "passive"))
      (node (ref "SW1") (pin "2") (pinfunction "2_2") (pintype "passive"))
      (node (ref "U5") (pin "38") (pinfunction "START_38") (pintype "input"))
    )
    (net (code "29") (name "GND") (class "Default")
      (node (ref "C1") (pin "1") (pinfunction "1_1") (pintype "passive"))
      (node (ref "C10") (pin "1") (pinfunction "1_1") (pintype "passive"))
      (node (ref "C11") (pin "1") (pinfunction "1_1") (pintype "passive"))
      (node (ref "C2") (pin "1") (pinfunction "1_1") (pintype "passive"))
      (node (ref "C3") (pin "1") (pinfunction "1_1") (pintype "passive"))
      (node (ref "C32") (pin "1") (pinfunction "1_1") (pintype "passive"))
      (node (ref "C33") (pin "1") (pinfunction "1_1") (pintype "passive"))
      (node (ref "C34") (pin "1") (pinfunction "1_1") (pintype "passive"))
      (node (ref "C35") (pin "1") (pinfunction "1_1") (pintype "passive"))
      (node (ref "C4") (pin "1") (pinfunction "1_1") (pintype "passive"))
      (node (ref "C5") (pin "1") (pinfunction "1_1") (pintype "passive"))
      (node (ref "C6") (pin "2") (pinfunction "2_2") (pintype "passive"))
      (node (ref "C8") (pin "1") (pinfunction "1_1") (pintype "passive"))
      (node (ref "C9") (pin "1") (pinfunction "1_1") (pintype "passive"))
      (node (ref "D1_power1") (pin "1") (pinfunction "C_1") (pintype "passive"))
      (node (ref "D2_ADS1") (pin "1") (pinfunction "C_1") (pintype "passive"))
      (node (ref "J1-A") (pin "14") (pinfunction "14_14") (pintype "passive"))
      (node (ref "J1-A") (pin "20") (pinfunction "20_20") (pintype "passive"))
      (node (ref "J1-A") (pin "25") (pinfunction "25_25") (pintype "passive"))
      (node (ref "J1-A") (pin "30") (pinfunction "30_30") (pintype "passive"))
      (node (ref "J1-A") (pin "34") (pinfunction "34_34") (pintype "passive"))
      (node (ref "J1-A") (pin "39") (pinfunction "39_39") (pintype "passive"))
      (node (ref "J1-A") (pin "6") (pinfunction "6_6") (pintype "passive"))
      (node (ref "J1-A") (pin "9") (pinfunction "9_9") (pintype "passive"))
      (node (ref "J1-B-") (pin "14") (pinfunction "14_14") (pintype "passive"))
      (node (ref "J1-B-") (pin "20") (pinfunction "20_20") (pintype "passive"))
      (node (ref "J1-B-") (pin "25") (pinfunction "25_25") (pintype "passive"))
      (node (ref "J1-B-") (pin "30") (pinfunction "30_30") (pintype "passive"))
      (node (ref "J1-B-") (pin "34") (pinfunction "34_34") (pintype "passive"))
      (node (ref "J1-B-") (pin "39") (pinfunction "39_39") (pintype "passive"))
      (node (ref "J1-B-") (pin "6") (pinfunction "6_6") (pintype "passive"))
      (node (ref "J1-B-") (pin "9") (pinfunction "9_9") (pintype "passive"))
      (node (ref "J1-C-") (pin "14") (pinfunction "14_14") (pintype "passive"))
      (node (ref "J1-C-") (pin "20") (pinfunction "20_20") (pintype "passive"))
      (node (ref "J1-C-") (pin "25") (pinfunction "25_25") (pintype "passive"))
      (node (ref "J1-C-") (pin "30") (pinfunction "30_30") (pintype "passive"))
      (node (ref "J1-C-") (pin "34") (pinfunction "34_34") (pintype "passive"))
      (node (ref "J1-C-") (pin "39") (pinfunction "39_39") (pintype "passive"))
      (node (ref "J1-C-") (pin "6") (pinfunction "6_6") (pintype "passive"))
      (node (ref "J1-C-") (pin "9") (pinfunction "9_9") (pintype "passive"))
      (node (ref "JMP1-R") (pin "1") (pinfunction "1_1") (pintype "passive"))
      (node (ref "JMP1-S") (pin "1") (pinfunction "1_1") (pintype "passive"))
      (node (ref "JMP2-3") (pin "1") (pinfunction "1_1") (pintype "passive"))
      (node (ref "JMP2-R") (pin "1") (pinfunction "1_1") (pintype "passive"))
      (node (ref "JMP3-R") (pin "1") (pinfunction "1_1") (pintype "passive"))
      (node (ref "JMP3-S") (pin "1") (pinfunction "1_1") (pintype "passive"))
      (node (ref "R11") (pin "1") (pinfunction "1_1") (pintype "passive"))
      (node (ref "R2") (pin "2") (pinfunction "2_2") (pintype "passive"))
      (node (ref "R27") (pin "1") (pinfunction "1_1") (pintype "passive"))
      (node (ref "R28") (pin "1") (pinfunction "1_1") (pintype "passive"))
      (node (ref "R3") (pin "2") (pinfunction "2_2") (pintype "passive"))
      (node (ref "R4") (pin "2") (pinfunction "2_2") (pintype "passive"))
      (node (ref "R8") (pin "2") (pinfunction "2_2") (pintype "passive"))
      (node (ref "U1") (pin "11") (pinfunction "GND_11") (pintype "power_in"))
      (node (ref "U1") (pin "5") (pinfunction "ILIM_5") (pintype "passive"))
      (node (ref "U1") (pin "8") (pinfunction "GND_8") (pintype "open_emitter"))
      (node (ref "U2") (pin "11") (pinfunction "GND_11") (pintype "power_in"))
      (node (ref "U2") (pin "5") (pinfunction "ILIM_5") (pintype "passive"))
      (node (ref "U2") (pin "8") (pinfunction "GND_8") (pintype "open_emitter"))
      (node (ref "U3") (pin "3") (pinfunction "GND_3") (pintype "power_in"))
      (node (ref "U3") (pin "6") (pinfunction "LV_6") (pintype "input"))
      (node (ref "U4") (pin "9") (pinfunction "GND_9") (pintype "power_in"))
      (node (ref "U5") (pin "31") (pinfunction "RESV1_31") (pintype "power_in"))
      (node (ref "U5") (pin "33") (pinfunction "DGND_33") (pintype "power_in"))
      (node (ref "U5") (pin "41") (pinfunction "DAISY_IN_41") (pintype "input"))
      (node (ref "U5") (pin "49") (pinfunction "DGND_49") (pintype "power_in"))
      (node (ref "U5") (pin "51") (pinfunction "DGND_51") (pintype "power_in"))
    )
    (net (code "30") (name "Net-(C30-Pad1)") (class "Default")
      (node (ref "C30") (pin "1") (pinfunction "1_1") (pintype "passive"))
      (node (ref "C31") (pin "1") (pinfunction "1_1") (pintype "passive"))
    )
    (net (code "31") (name "Net-(D1_power1-A)") (class "Default")
      (node (ref "D1_power1") (pin "2") (pinfunction "A_2") (pintype "passive"))
      (node (ref "R1_power1") (pin "1") (pinfunction "1_1") (pintype "passive"))
    )
    (net (code "32") (name "Net-(D2-BLUE_A)") (class "Default")
      (node (ref "D2") (pin "4") (pinfunction "BLUE_A_4") (pintype "passive"))
      (node (ref "R29") (pin "1") (pinfunction "1_1") (pintype "passive"))
    )
    (net (code "33") (name "Net-(D2-COMMON_CATHODE)") (class "Default")
      (node (ref "D2") (pin "1") (pinfunction "COMMON_CATHODE_1") (pintype "passive"))
      (node (ref "R28") (pin "2") (pinfunction "2_2") (pintype "passive"))
    )
    (net (code "34") (name "Net-(D2-GREEN_A)") (class "Default")
      (node (ref "D2") (pin "3") (pinfunction "GREEN_A_3") (pintype "passive"))
      (node (ref "R30") (pin "1") (pinfunction "1_1") (pintype "passive"))
    )
    (net (code "35") (name "Net-(D2-RED_A)") (class "Default")
      (node (ref "D2") (pin "2") (pinfunction "RED_A_2") (pintype "passive"))
      (node (ref "R31") (pin "1") (pinfunction "1_1") (pintype "passive"))
    )
    (net (code "36") (name "Net-(D2_ADS1-A)") (class "Default")
      (node (ref "D2_ADS1") (pin "2") (pinfunction "A_2") (pintype "passive"))
      (node (ref "R7LED1") (pin "2") (pinfunction "2_2") (pintype "passive"))
    )
    (net (code "37") (name "Net-(R27-Pad2)") (class "Default")
      (node (ref "R27") (pin "2") (pinfunction "2_2") (pintype "passive"))
      (node (ref "SW1") (pin "4") (pinfunction "4_4") (pintype "passive"))
    )
    (net (code "38") (name "Net-(U1-SET)") (class "Default")
      (node (ref "C3") (pin "2") (pinfunction "2_2") (pintype "passive"))
      (node (ref "R2") (pin "1") (pinfunction "1_1") (pintype "passive"))
      (node (ref "U1") (pin "7") (pinfunction "SET_7") (pintype "input"))
    )
    (net (code "39") (name "Net-(U2-SET)") (class "Default")
      (node (ref "C6") (pin "1") (pinfunction "1_1") (pintype "passive"))
      (node (ref "R3") (pin "1") (pinfunction "1_1") (pintype "passive"))
      (node (ref "U2") (pin "7") (pinfunction "SET_7") (pintype "input"))
    )
    (net (code "40") (name "Net-(U3-C1+)") (class "Default")
      (node (ref "C7") (pin "2") (pinfunction "2_2") (pintype "passive"))
      (node (ref "U3") (pin "2") (pinfunction "C1+_2") (pintype "input"))
    )
    (net (code "41") (name "Net-(U3-C1-)") (class "Default")
      (node (ref "C7") (pin "1") (pinfunction "1_1") (pintype "passive"))
      (node (ref "U3") (pin "4") (pinfunction "C1-_4") (pintype "input"))
    )
    (net (code "42") (name "Net-(U4-SET)") (class "Default")
      (node (ref "C11") (pin "2") (pinfunction "2_2") (pintype "passive"))
      (node (ref "R4") (pin "1") (pinfunction "1_1") (pintype "passive"))
      (node (ref "U4") (pin "8") (pinfunction "SET_8") (pintype "input"))
    )
    (net (code "43") (name "Net-(U5A-BIASIN)") (class "Default")
      (node (ref "R32") (pin "1") (pinfunction "1_1") (pintype "passive"))
      (node (ref "U5") (pin "62") (pinfunction "BIASIN_62") (pintype "input"))
    )
    (net (code "44") (name "Net-(U5A-BIASINV)") (class "Default")
      (node (ref "C27") (pin "1") (pinfunction "1_1") (pintype "passive"))
      (node (ref "R21") (pin "2") (pinfunction "2_2") (pintype "passive"))
      (node (ref "R32") (pin "2") (pinfunction "2_2") (pintype "passive"))
      (node (ref "U5") (pin "61") (pinfunction "BIASINV_61") (pintype "input"))
    )
    (net (code "45") (name "Net-(U5A-BIASOUT)") (class "Default")
      (node (ref "C27") (pin "2") (pinfunction "2_2") (pintype "passive"))
      (node (ref "R20") (pin "2") (pinfunction "2_2") (pintype "passive"))
      (node (ref "R21") (pin "1") (pinfunction "1_1") (pintype "passive"))
      (node (ref "U5") (pin "63") (pinfunction "BIASOUT_63") (pintype "output"))
    )
    (net (code "46") (name "Net-(U5A-CLKSEL)") (class "Default")
      (node (ref "R11") (pin "2") (pinfunction "2_2") (pintype "passive"))
      (node (ref "R22") (pin "2") (pinfunction "2_2") (pintype "passive"))
      (node (ref "U5") (pin "52") (pinfunction "CLKSEL_52") (pintype "input"))
    )
    (net (code "47") (name "Net-(U5A-GPIO1)") (class "Default")
      (node (ref "R8") (pin "1") (pinfunction "1_1") (pintype "passive"))
      (node (ref "U5") (pin "42") (pinfunction "GPIO1_42") (pintype "bidirectional"))
      (node (ref "U5") (pin "44") (pinfunction "GPIO2_44") (pintype "bidirectional"))
      (node (ref "U5") (pin "45") (pinfunction "GPIO3_45") (pintype "bidirectional"))
    )
    (net (code "48") (name "Net-(U5A-GPIO4)") (class "Default")
      (node (ref "R7LED1") (pin "1") (pinfunction "1_1") (pintype "passive"))
      (node (ref "U5") (pin "46") (pinfunction "GPIO4_46") (pintype "bidirectional"))
    )
    (net (code "49") (name "Net-(U5A-IN1P)") (class "Default")
      (node (ref "C19") (pin "2") (pinfunction "2_2") (pintype "passive"))
      (node (ref "R12") (pin "2") (pinfunction "2_2") (pintype "passive"))
      (node (ref "U5") (pin "16") (pinfunction "IN1P_16") (pintype "input"))
    )
    (net (code "50") (name "Net-(U5A-IN2P)") (class "Default")
      (node (ref "C20") (pin "2") (pinfunction "2_2") (pintype "passive"))
      (node (ref "R13") (pin "2") (pinfunction "2_2") (pintype "passive"))
      (node (ref "U5") (pin "14") (pinfunction "IN2P_14") (pintype "input"))
    )
    (net (code "51") (name "Net-(U5A-IN3P)") (class "Default")
      (node (ref "C21") (pin "2") (pinfunction "2_2") (pintype "passive"))
      (node (ref "R14") (pin "2") (pinfunction "2_2") (pintype "passive"))
      (node (ref "U5") (pin "12") (pinfunction "IN3P_12") (pintype "input"))
    )
    (net (code "52") (name "Net-(U5A-IN4P)") (class "Default")
      (node (ref "C22") (pin "2") (pinfunction "2_2") (pintype "passive"))
      (node (ref "R15") (pin "2") (pinfunction "2_2") (pintype "passive"))
      (node (ref "U5") (pin "10") (pinfunction "IN4P_10") (pintype "input"))
    )
    (net (code "53") (name "Net-(U5A-IN5P)") (class "Default")
      (node (ref "C23") (pin "2") (pinfunction "2_2") (pintype "passive"))
      (node (ref "R16") (pin "2") (pinfunction "2_2") (pintype "passive"))
      (node (ref "U5") (pin "8") (pinfunction "IN5P_8") (pintype "input"))
    )
    (net (code "54") (name "Net-(U5A-IN6P)") (class "Default")
      (node (ref "C24") (pin "2") (pinfunction "2_2") (pintype "passive"))
      (node (ref "R17") (pin "2") (pinfunction "2_2") (pintype "passive"))
      (node (ref "U5") (pin "6") (pinfunction "IN6P_6") (pintype "input"))
    )
    (net (code "55") (name "Net-(U5A-IN7P)") (class "Default")
      (node (ref "C25") (pin "2") (pinfunction "2_2") (pintype "passive"))
      (node (ref "R18") (pin "2") (pinfunction "2_2") (pintype "passive"))
      (node (ref "U5") (pin "4") (pinfunction "IN7P_4") (pintype "input"))
    )
    (net (code "56") (name "Net-(U5A-IN8P)") (class "Default")
      (node (ref "C26") (pin "2") (pinfunction "2_2") (pintype "passive"))
      (node (ref "R19") (pin "2") (pinfunction "2_2") (pintype "passive"))
      (node (ref "U5") (pin "2") (pinfunction "IN8P_2") (pintype "input"))
    )
    (net (code "57") (name "Net-(U5A-SRB1)") (class "Default")
      (node (ref "C19") (pin "1") (pinfunction "1_1") (pintype "passive"))
      (node (ref "C20") (pin "1") (pinfunction "1_1") (pintype "passive"))
      (node (ref "C21") (pin "1") (pinfunction "1_1") (pintype "passive"))
      (node (ref "C22") (pin "1") (pinfunction "1_1") (pintype "passive"))
      (node (ref "C23") (pin "1") (pinfunction "1_1") (pintype "passive"))
      (node (ref "C24") (pin "1") (pinfunction "1_1") (pintype "passive"))
      (node (ref "C25") (pin "1") (pinfunction "1_1") (pintype "passive"))
      (node (ref "C26") (pin "1") (pinfunction "1_1") (pintype "passive"))
      (node (ref "R33") (pin "2") (pinfunction "2_2") (pintype "passive"))
      (node (ref "U5") (pin "17") (pinfunction "SRB1_17") (pintype "input"))
    )
    (net (code "58") (name "Net-(U5A-SRB2)") (class "Default")
      (node (ref "R23") (pin "1") (pinfunction "1_1") (pintype "passive"))
      (node (ref "U5") (pin "18") (pinfunction "SRB2_18") (pintype "input"))
    )
    (net (code "59") (name "Net-(U5A-VCAP1)") (class "Default")
      (node (ref "C15_Vcap1") (pin "1") (pinfunction "1_1") (pintype "passive"))
      (node (ref "U5") (pin "28") (pinfunction "VCAP1_28") (pintype "passive"))
    )
    (net (code "60") (name "Net-(U5A-VCAP2)") (class "Default")
      (node (ref "C14_Vcap2") (pin "2") (pinfunction "2_2") (pintype "passive"))
      (node (ref "U5") (pin "30") (pinfunction "VCAP2_30") (pintype "passive"))
    )
    (net (code "61") (name "Net-(U5A-VCAP3)") (class "Default")
      (node (ref "C28") (pin "2") (pinfunction "2_2") (pintype "passive"))
      (node (ref "C29") (pin "2") (pinfunction "2_2") (pintype "passive"))
      (node (ref "U5") (pin "55") (pinfunction "VCAP3_55") (pintype "passive"))
    )
    (net (code "62") (name "Net-(U5A-VCAP4)") (class "Default")
      (node (ref "C16_Vcap4") (pin "2") (pinfunction "2_2") (pintype "passive"))
      (node (ref "U5") (pin "26") (pinfunction "VCAP4_26") (pintype "passive"))
    )
    (net (code "63") (name "Net-(U5A-VREFP)") (class "Default")
      (node (ref "C17") (pin "1") (pinfunction "1_1") (pintype "passive"))
      (node (ref "C18") (pin "2") (pinfunction "2_2") (pintype "passive"))
      (node (ref "U5") (pin "24") (pinfunction "VREFP_24") (pintype "passive"))
    )
    (net (code "64") (name "Net-(U5A-~{PWDN})") (class "Default")
      (node (ref "R10") (pin "2") (pinfunction "2_2") (pintype "passive"))
      (node (ref "U5") (pin "35") (pinfunction "~{PWDN}_35") (pintype "input"))
    )
    (net (code "65") (name "Net-(U5A-~{RESET})") (class "Default")
      (node (ref "R9") (pin "2") (pinfunction "2_2") (pintype "passive"))
      (node (ref "U5") (pin "36") (pinfunction "~{RESET}_36") (pintype "input"))
    )
    (net (code "66") (name "unconnected-(J1-A-Pad1)") (class "Default")
      (node (ref "J1-A") (pin "1") (pinfunction "1_1") (pintype "passive"))
    )
    (net (code "67") (name "unconnected-(J1-A-Pad3)") (class "Default")
      (node (ref "J1-A") (pin "3") (pinfunction "3_3") (pintype "passive"))
    )
    (net (code "68") (name "unconnected-(J1-A-Pad5)") (class "Default")
      (node (ref "J1-A") (pin "5") (pinfunction "5_5") (pintype "passive"))
    )
    (net (code "69") (name "unconnected-(J1-A-Pad8)") (class "Default")
      (node (ref "J1-A") (pin "8") (pinfunction "8_8") (pintype "passive"))
    )
    (net (code "70") (name "unconnected-(J1-A-Pad10)") (class "Default")
      (node (ref "J1-A") (pin "10") (pinfunction "10_10") (pintype "passive"))
    )
    (net (code "71") (name "unconnected-(J1-A-Pad12)") (class "Default")
      (node (ref "J1-A") (pin "12") (pinfunction "12_12") (pintype "passive"))
    )
    (net (code "72") (name "unconnected-(J1-A-Pad15)") (class "Default")
      (node (ref "J1-A") (pin "15") (pinfunction "15_15") (pintype "passive"))
    )
    (net (code "73") (name "unconnected-(J1-A-Pad16)") (class "Default")
      (node (ref "J1-A") (pin "16") (pinfunction "16_16") (pintype "passive"))
    )
    (net (code "74") (name "unconnected-(J1-A-Pad17)") (class "Default")
      (node (ref "J1-A") (pin "17") (pinfunction "17_17") (pintype "passive"))
    )
    (net (code "75") (name "unconnected-(J1-A-Pad18)") (class "Default")
      (node (ref "J1-A") (pin "18") (pinfunction "18_18") (pintype "passive"))
    )
    (net (code "76") (name "unconnected-(J1-A-Pad22)") (class "Default")
      (node (ref "J1-A") (pin "22") (pinfunction "22_22") (pintype "passive"))
    )
    (net (code "77") (name "unconnected-(J1-A-Pad26)") (class "Default")
      (node (ref "J1-A") (pin "26") (pinfunction "26_26") (pintype "passive"))
    )
    (net (code "78") (name "unconnected-(J1-A-Pad27)") (class "Default")
      (node (ref "J1-A") (pin "27") (pinfunction "27_27") (pintype "passive"))
    )
    (net (code "79") (name "unconnected-(J1-A-Pad28)") (class "Default")
      (node (ref "J1-A") (pin "28") (pinfunction "28_28") (pintype "passive"))
    )
    (net (code "80") (name "unconnected-(J1-A-Pad32)") (class "Default")
      (node (ref "J1-A") (pin "32") (pinfunction "32_32") (pintype "passive"))
    )
    (net (code "81") (name "unconnected-(J1-A-Pad36)") (class "Default")
      (node (ref "J1-A") (pin "36") (pinfunction "36_36") (pintype "passive"))
    )
    (net (code "82") (name "unconnected-(J1-A-Pad38)") (class "Default")
      (node (ref "J1-A") (pin "38") (pinfunction "38_38") (pintype "passive"))
    )
    (net (code "83") (name "unconnected-(J1-A-Pad40)") (class "Default")
      (node (ref "J1-A") (pin "40") (pinfunction "40_40") (pintype "passive"))
    )
    (net (code "84") (name "unconnected-(J1-B--Pad1)") (class "Default")
      (node (ref "J1-B-") (pin "1") (pinfunction "1_1") (pintype "passive"))
    )
    (net (code "85") (name "unconnected-(J1-B--Pad3)") (class "Default")
      (node (ref "J1-B-") (pin "3") (pinfunction "3_3") (pintype "passive"))
    )
    (net (code "86") (name "unconnected-(J1-B--Pad5)") (class "Default")
      (node (ref "J1-B-") (pin "5") (pinfunction "5_5") (pintype "passive"))
    )
    (net (code "87") (name "unconnected-(J1-B--Pad8)") (class "Default")
      (node (ref "J1-B-") (pin "8") (pinfunction "8_8") (pintype "passive"))
    )
    (net (code "88") (name "unconnected-(J1-B--Pad10)") (class "Default")
      (node (ref "J1-B-") (pin "10") (pinfunction "10_10") (pintype "passive"))
    )
    (net (code "89") (name "unconnected-(J1-B--Pad12)") (class "Default")
      (node (ref "J1-B-") (pin "12") (pinfunction "12_12") (pintype "passive"))
    )
    (net (code "90") (name "unconnected-(J1-B--Pad15)") (class "Default")
      (node (ref "J1-B-") (pin "15") (pinfunction "15_15") (pintype "passive"))
    )
    (net (code "91") (name "unconnected-(J1-B--Pad16)") (class "Default")
      (node (ref "J1-B-") (pin "16") (pinfunction "16_16") (pintype "passive"))
    )
    (net (code "92") (name "unconnected-(J1-B--Pad17)") (class "Default")
      (node (ref "J1-B-") (pin "17") (pinfunction "17_17") (pintype "passive"))
    )
    (net (code "93") (name "unconnected-(J1-B--Pad18)") (class "Default")
      (node (ref "J1-B-") (pin "18") (pinfunction "18_18") (pintype "passive"))
    )
    (net (code "94") (name "unconnected-(J1-B--Pad22)") (class "Default")
      (node (ref "J1-B-") (pin "22") (pinfunction "22_22") (pintype "passive"))
    )
    (net (code "95") (name "unconnected-(J1-B--Pad26)") (class "Default")
      (node (ref "J1-B-") (pin "26") (pinfunction "26_26") (pintype "passive"))
    )
    (net (code "96") (name "unconnected-(J1-B--Pad27)") (class "Default")
      (node (ref "J1-B-") (pin "27") (pinfunction "27_27") (pintype "passive"))
    )
    (net (code "97") (name "unconnected-(J1-B--Pad28)") (class "Default")
      (node (ref "J1-B-") (pin "28") (pinfunction "28_28") (pintype "passive"))
    )
    (net (code "98") (name "unconnected-(J1-B--Pad32)") (class "Default")
      (node (ref "J1-B-") (pin "32") (pinfunction "32_32") (pintype "passive"))
    )
    (net (code "99") (name "unconnected-(J1-B--Pad36)") (class "Default")
      (node (ref "J1-B-") (pin "36") (pinfunction "36_36") (pintype "passive"))
    )
    (net (code "100") (name "unconnected-(J1-B--Pad38)") (class "Default")
      (node (ref "J1-B-") (pin "38") (pinfunction "38_38") (pintype "passive"))
    )
    (net (code "101") (name "unconnected-(J1-B--Pad40)") (class "Default")
      (node (ref "J1-B-") (pin "40") (pinfunction "40_40") (pintype "passive"))
    )
    (net (code "102") (name "unconnected-(J1-C--Pad1)") (class "Default")
      (node (ref "J1-C-") (pin "1") (pinfunction "1_1") (pintype "passive"))
    )
    (net (code "103") (name "unconnected-(J1-C--Pad3)") (class "Default")
      (node (ref "J1-C-") (pin "3") (pinfunction "3_3") (pintype "passive"))
    )
    (net (code "104") (name "unconnected-(J1-C--Pad5)") (class "Default")
      (node (ref "J1-C-") (pin "5") (pinfunction "5_5") (pintype "passive"))
    )
    (net (code "105") (name "unconnected-(J1-C--Pad8)") (class "Default")
      (node (ref "J1-C-") (pin "8") (pinfunction "8_8") (pintype "passive"))
    )
    (net (code "106") (name "unconnected-(J1-C--Pad10)") (class "Default")
      (node (ref "J1-C-") (pin "10") (pinfunction "10_10") (pintype "passive"))
    )
    (net (code "107") (name "unconnected-(J1-C--Pad12)") (class "Default")
      (node (ref "J1-C-") (pin "12") (pinfunction "12_12") (pintype "passive"))
    )
    (net (code "108") (name "unconnected-(J1-C--Pad15)") (class "Default")
      (node (ref "J1-C-") (pin "15") (pinfunction "15_15") (pintype "passive"))
    )
    (net (code "109") (name "unconnected-(J1-C--Pad16)") (class "Default")
      (node (ref "J1-C-") (pin "16") (pinfunction "16_16") (pintype "passive"))
    )
    (net (code "110") (name "unconnected-(J1-C--Pad17)") (class "Default")
      (node (ref "J1-C-") (pin "17") (pinfunction "17_17") (pintype "passive"))
    )
    (net (code "111") (name "unconnected-(J1-C--Pad18)") (class "Default")
      (node (ref "J1-C-") (pin "18") (pinfunction "18_18") (pintype "passive"))
    )
    (net (code "112") (name "unconnected-(J1-C--Pad22)") (class "Default")
      (node (ref "J1-C-") (pin "22") (pinfunction "22_22") (pintype "passive"))
    )
    (net (code "113") (name "unconnected-(J1-C--Pad26)") (class "Default")
      (node (ref "J1-C-") (pin "26") (pinfunction "26_26") (pintype "passive"))
    )
    (net (code "114") (name "unconnected-(J1-C--Pad27)") (class "Default")
      (node (ref "J1-C-") (pin "27") (pinfunction "27_27") (pintype "passive"))
    )
    (net (code "115") (name "unconnected-(J1-C--Pad28)") (class "Default")
      (node (ref "J1-C-") (pin "28") (pinfunction "28_28") (pintype "passive"))
    )
    (net (code "116") (name "unconnected-(J1-C--Pad32)") (class "Default")
      (node (ref "J1-C-") (pin "32") (pinfunction "32_32") (pintype "passive"))
    )
    (net (code "117") (name "unconnected-(J1-C--Pad36)") (class "Default")
      (node (ref "J1-C-") (pin "36") (pinfunction "36_36") (pintype "passive"))
    )
    (net (code "118") (name "unconnected-(J1-C--Pad38)") (class "Default")
      (node (ref "J1-C-") (pin "38") (pinfunction "38_38") (pintype "passive"))
    )
    (net (code "119") (name "unconnected-(J1-C--Pad40)") (class "Default")
      (node (ref "J1-C-") (pin "40") (pinfunction "40_40") (pintype "passive"))
    )
    (net (code "120") (name "unconnected-(M1-PadS)") (class "Default")
      (node (ref "M1") (pin "S") (pinfunction "S_S") (pintype "passive"))
    )
    (net (code "121") (name "unconnected-(M2-PadS)") (class "Default")
      (node (ref "M2") (pin "S") (pinfunction "S_S") (pintype "passive"))
    )
    (net (code "122") (name "unconnected-(M3-PadS)") (class "Default")
      (node (ref "M3") (pin "S") (pinfunction "S_S") (pintype "passive"))
    )
    (net (code "123") (name "unconnected-(M4-PadS)") (class "Default")
      (node (ref "M4") (pin "S") (pinfunction "S_S") (pintype "passive"))
    )
    (net (code "124") (name "unconnected-(U1-PG-Pad4)") (class "Default")
      (node (ref "U1") (pin "4") (pinfunction "PG_4") (pintype "open_collector"))
    )
    (net (code "125") (name "unconnected-(U2-PG-Pad4)") (class "Default")
      (node (ref "U2") (pin "4") (pinfunction "PG_4") (pintype "open_collector"))
    )
    (net (code "126") (name "unconnected-(U3-FC-Pad1)") (class "Default")
      (node (ref "U3") (pin "1") (pinfunction "FC_1") (pintype "input"))
    )
    (net (code "127") (name "unconnected-(U3-OSC-Pad7)") (class "Default")
      (node (ref "U3") (pin "7") (pinfunction "OSC_7") (pintype "input"))
    )
    (net (code "128") (name "unconnected-(U4-ILIM-Pad6)") (class "Default")
      (node (ref "U4") (pin "6") (pinfunction "ILIM_6") (pintype "input"))
    )
    (net (code "129") (name "unconnected-(U4-PG-Pad4)") (class "Default")
      (node (ref "U4") (pin "4") (pinfunction "PG_4") (pintype "output"))
    )
    (net (code "130") (name "unconnected-(U4-VIOC-Pad7)") (class "Default")
      (node (ref "U4") (pin "7") (pinfunction "VIOC_7") (pintype "bidirectional"))
    )
    (net (code "131") (name "unconnected-(U5A-CLK-Pad37)") (class "Default")
      (node (ref "U5") (pin "37") (pinfunction "CLK_37") (pintype "bidirectional"))
    )
    (net (code "132") (name "unconnected-(U5A-IN1N-Pad15)") (class "Default")
      (node (ref "U5") (pin "15") (pinfunction "IN1N_15") (pintype "input"))
    )
    (net (code "133") (name "unconnected-(U5A-IN2N-Pad13)") (class "Default")
      (node (ref "U5") (pin "13") (pinfunction "IN2N_13") (pintype "input"))
    )
    (net (code "134") (name "unconnected-(U5A-IN3N-Pad11)") (class "Default")
      (node (ref "U5") (pin "11") (pinfunction "IN3N_11") (pintype "input"))
    )
    (net (code "135") (name "unconnected-(U5A-IN4N-Pad9)") (class "Default")
      (node (ref "U5") (pin "9") (pinfunction "IN4N_9") (pintype "input"))
    )
    (net (code "136") (name "unconnected-(U5A-IN5N-Pad7)") (class "Default")
      (node (ref "U5") (pin "7") (pinfunction "IN5N_7") (pintype "input"))
    )
    (net (code "137") (name "unconnected-(U5A-IN6N-Pad5)") (class "Default")
      (node (ref "U5") (pin "5") (pinfunction "IN6N_5") (pintype "input"))
    )
    (net (code "138") (name "unconnected-(U5A-IN7N-Pad3)") (class "Default")
      (node (ref "U5") (pin "3") (pinfunction "IN7N_3") (pintype "input"))
    )
    (net (code "139") (name "unconnected-(U5A-IN8N-Pad1)") (class "Default")
      (node (ref "U5") (pin "1") (pinfunction "IN8N_1") (pintype "input"))
    )
    (net (code "140") (name "unconnected-(U5A-NC-Pad27)") (class "Default")
      (node (ref "U5") (pin "27") (pinfunction "NC_27") (pintype "passive"))
    )
    (net (code "141") (name "unconnected-(U5A-NC-Pad29)") (class "Default")
      (node (ref "U5") (pin "29") (pinfunction "NC_29") (pintype "passive"))
    )
    (net (code "142") (name "unconnected-(U5A-RESERVED-Pad64)") (class "Default")
      (node (ref "U5") (pin "64") (pinfunction "RESERVED_64") (pintype "passive"))
    )
  )
)
